# core6.net
KiCad netlist of a schematic drawn in EAGLE
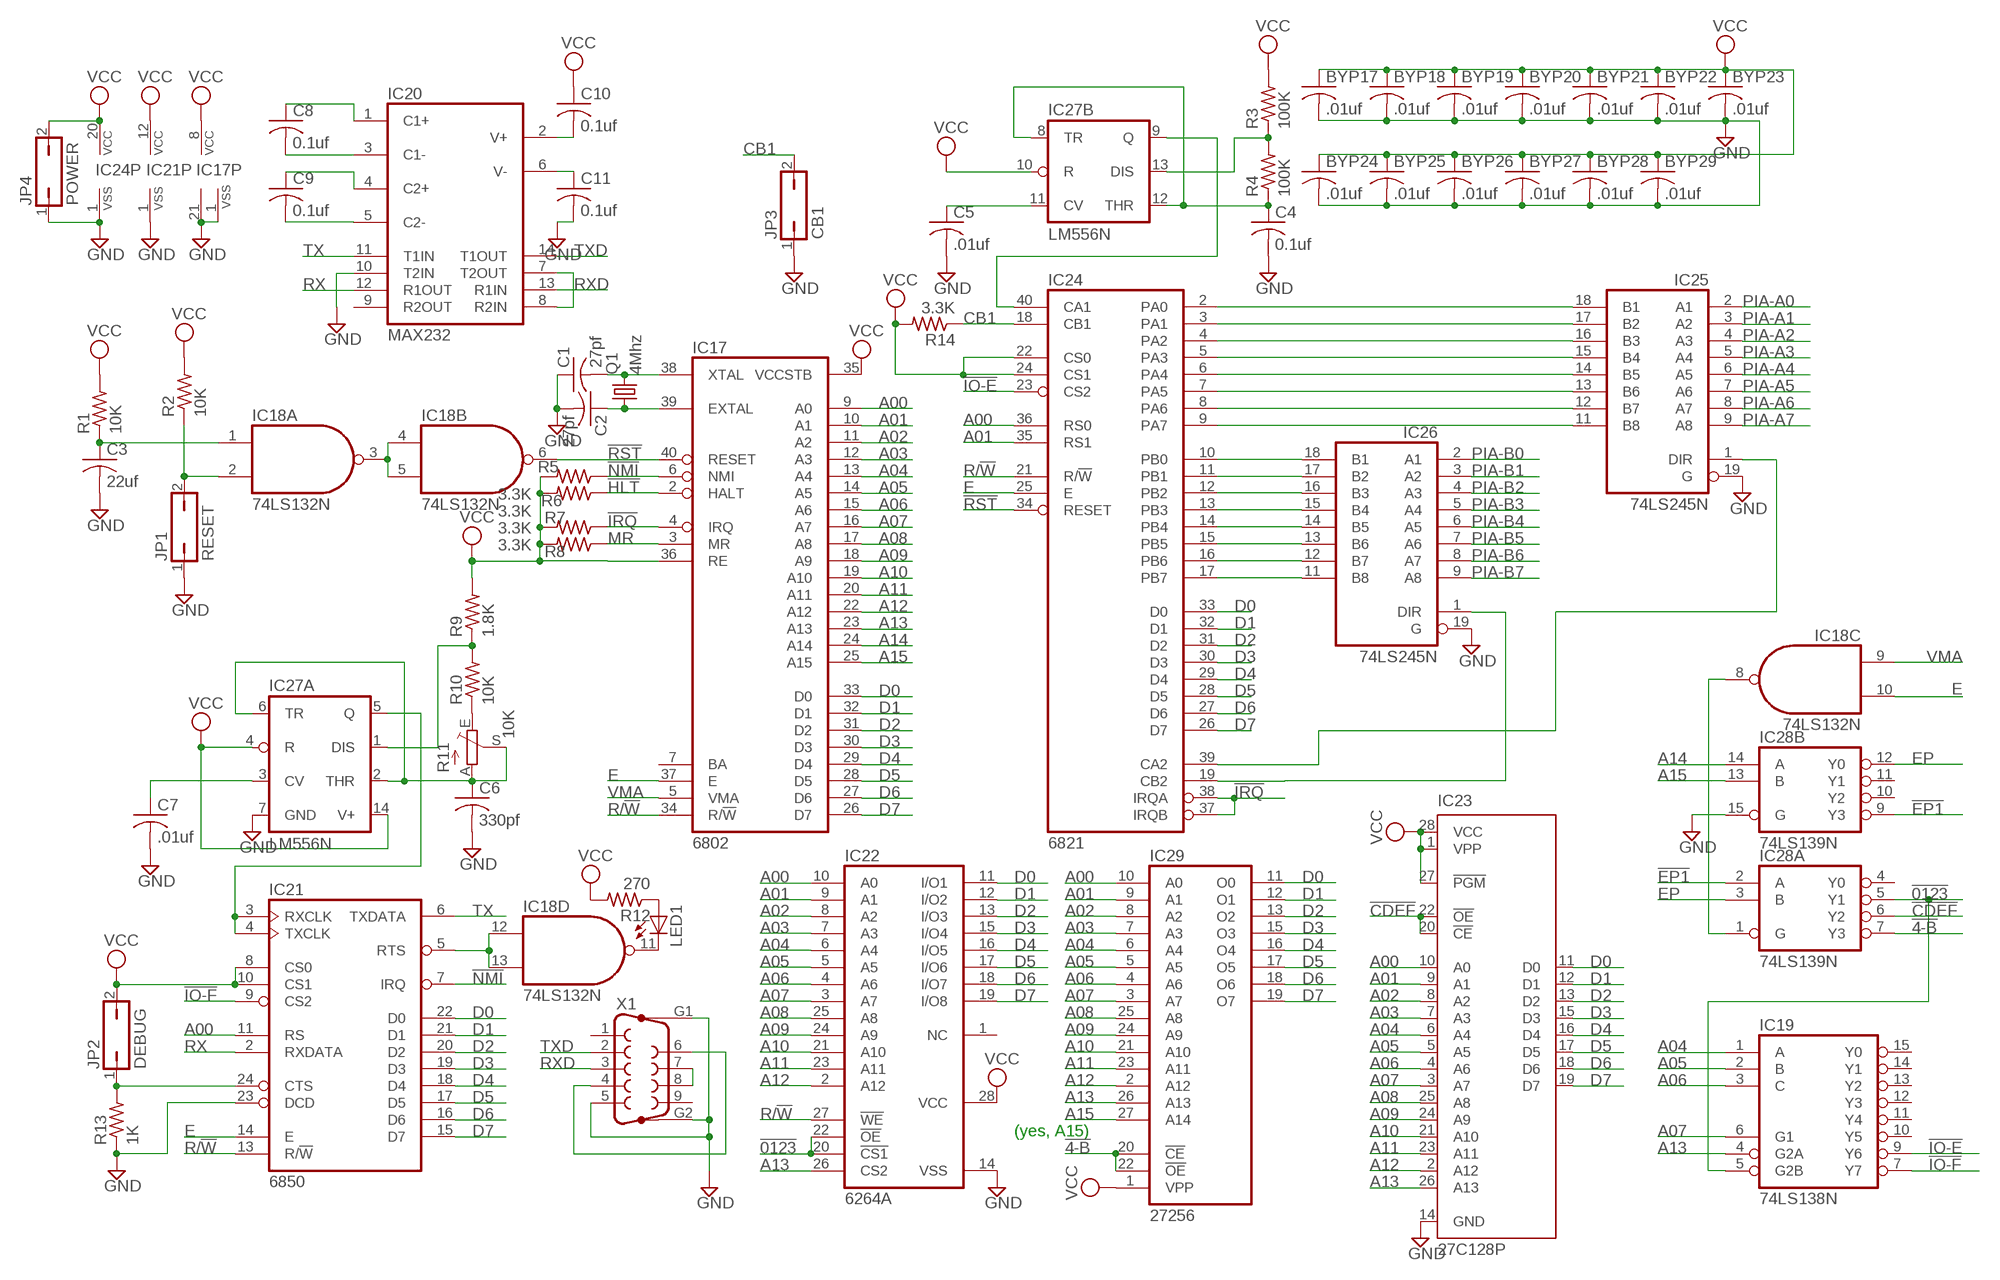
[diagram p0: schematic, sheet 1]
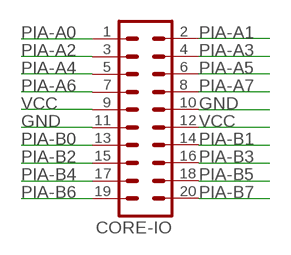
[diagram p1: schematic, sheet 2]

(export (version "E")
  (design (tool "Eeschema 10.0.6"))
  (components
    (comp (ref "BYP17")
      (value ".01uf")
      (footprint "eagle-import:C050-025X075")
      (libsource (lib "eagle-import") (part "C-US050-025X075"))
    )
    (comp (ref "BYP18")
      (value ".01uf")
      (footprint "eagle-import:C050-025X075")
      (libsource (lib "eagle-import") (part "C-US050-025X075"))
    )
    (comp (ref "BYP19")
      (value ".01uf")
      (footprint "eagle-import:C050-025X075")
      (libsource (lib "eagle-import") (part "C-US050-025X075"))
    )
    (comp (ref "BYP20")
      (value ".01uf")
      (footprint "eagle-import:C050-025X075")
      (libsource (lib "eagle-import") (part "C-US050-025X075"))
    )
    (comp (ref "BYP21")
      (value ".01uf")
      (footprint "eagle-import:C050-025X075")
      (libsource (lib "eagle-import") (part "C-US050-025X075"))
    )
    (comp (ref "BYP22")
      (value ".01uf")
      (footprint "eagle-import:C050-025X075")
      (libsource (lib "eagle-import") (part "C-US050-025X075"))
    )
    (comp (ref "BYP23")
      (value ".01uf")
      (footprint "eagle-import:C050-025X075")
      (libsource (lib "eagle-import") (part "C-US050-025X075"))
    )
    (comp (ref "BYP24")
      (value ".01uf")
      (footprint "eagle-import:C050-025X075")
      (libsource (lib "eagle-import") (part "C-US050-025X075"))
    )
    (comp (ref "BYP25")
      (value ".01uf")
      (footprint "eagle-import:C050-025X075")
      (libsource (lib "eagle-import") (part "C-US050-025X075"))
    )
    (comp (ref "BYP26")
      (value ".01uf")
      (footprint "eagle-import:C050-025X075")
      (libsource (lib "eagle-import") (part "C-US050-025X075"))
    )
    (comp (ref "BYP27")
      (value ".01uf")
      (footprint "eagle-import:C050-025X075")
      (libsource (lib "eagle-import") (part "C-US050-025X075"))
    )
    (comp (ref "BYP28")
      (value ".01uf")
      (footprint "eagle-import:C050-025X075")
      (libsource (lib "eagle-import") (part "C-US050-025X075"))
    )
    (comp (ref "BYP29")
      (value ".01uf")
      (footprint "eagle-import:C050-025X075")
      (libsource (lib "eagle-import") (part "C-US050-025X075"))
    )
    (comp (ref "C1")
      (value "27pf")
      (footprint "eagle-import:C050-025X075")
      (libsource (lib "eagle-import") (part "C-US050-025X075"))
    )
    (comp (ref "C2")
      (value "27pf")
      (footprint "eagle-import:C050-025X075")
      (libsource (lib "eagle-import") (part "C-US050-025X075"))
    )
    (comp (ref "C3")
      (value "22uf")
      (footprint "eagle-import:C102-043X133")
      (libsource (lib "eagle-import") (part "C-US102-043X133"))
    )
    (comp (ref "C4")
      (value "0.1uf")
      (footprint "eagle-import:C050-025X075")
      (libsource (lib "eagle-import") (part "C-US050-025X075"))
    )
    (comp (ref "C5")
      (value ".01uf")
      (footprint "eagle-import:C050-025X075")
      (libsource (lib "eagle-import") (part "C-US050-025X075"))
    )
    (comp (ref "C6")
      (value "330pf")
      (footprint "eagle-import:C050-025X075")
      (libsource (lib "eagle-import") (part "C-US050-025X075"))
    )
    (comp (ref "C7")
      (value ".01uf")
      (footprint "eagle-import:C050-025X075")
      (libsource (lib "eagle-import") (part "C-US050-025X075"))
    )
    (comp (ref "C8")
      (value "0.1uf")
      (footprint "eagle-import:C050-025X075")
      (libsource (lib "eagle-import") (part "C-US050-025X075"))
    )
    (comp (ref "C9")
      (value "0.1uf")
      (footprint "eagle-import:C050-025X075")
      (libsource (lib "eagle-import") (part "C-US050-025X075"))
    )
    (comp (ref "C10")
      (value "0.1uf")
      (footprint "eagle-import:C050-025X075")
      (libsource (lib "eagle-import") (part "C-US050-025X075"))
    )
    (comp (ref "C11")
      (value "0.1uf")
      (footprint "eagle-import:C050-025X075")
      (libsource (lib "eagle-import") (part "C-US050-025X075"))
    )
    (comp (ref "IC17")
      (value "6802")
      (footprint "eagle-import:DIL40")
      (libsource (lib "eagle-import") (part "6802"))
    )
    (comp (ref "IC18")
      (value "74LS132N")
      (footprint "eagle-import:DIL14")
      (libsource (lib "eagle-import") (part "7400NLS"))
    )
    (comp (ref "IC19")
      (value "74LS138N")
      (footprint "eagle-import:DIL16")
      (libsource (lib "eagle-import") (part "74138NLS"))
    )
    (comp (ref "IC20")
      (value "MAX232")
      (footprint "eagle-import:DIL16")
      (fields (field (name "MF") "MAXIM") (field (name "MPN") "MAX232ACPE+"))
      (libsource (lib "eagle-import") (part "MAX232"))
    )
    (comp (ref "IC21")
      (value "6850")
      (footprint "eagle-import:DIL24")
      (fields (field (name "MF") "NTE ELECTRONICS") (field (name "MPN") "NTE6850"))
      (libsource (lib "eagle-import") (part "6850"))
    )
    (comp (ref "IC22")
      (value "6264A")
      (footprint "eagle-import:DIL28-6")
      (libsource (lib "eagle-import") (part "6264A"))
    )
    (comp (ref "IC23")
      (value "27C128P")
      (footprint "eagle-import:DIL28-6")
      (libsource (lib "eagle-import") (part "27128PC"))
    )
    (comp (ref "IC24")
      (value "6821")
      (footprint "eagle-import:DIL40")
      (fields (field (name "MF") "NTE ELECTRONICS") (field (name "MPN") "NTE6821"))
      (libsource (lib "eagle-import") (part "6821"))
    )
    (comp (ref "IC25")
      (value "74LS245N")
      (footprint "eagle-import:DIL20")
      (libsource (lib "eagle-import") (part "74245NLS"))
    )
    (comp (ref "IC26")
      (value "74LS245N")
      (footprint "eagle-import:DIL20")
      (libsource (lib "eagle-import") (part "74245NLS"))
    )
    (comp (ref "IC27")
      (value "LM556N")
      (footprint "eagle-import:DIL14")
      (libsource (lib "eagle-import") (part "556NLM"))
    )
    (comp (ref "IC28")
      (value "74LS139N")
      (footprint "eagle-import:DIL16")
      (libsource (lib "eagle-import") (part "74139NLS"))
    )
    (comp (ref "IC29")
      (value "27256")
      (footprint "eagle-import:DIL28")
      (libsource (lib "eagle-import") (part "27256"))
    )
    (comp (ref "JP1")
      (value "RESET")
      (footprint "eagle-import:JP1")
      (libsource (lib "eagle-import") (part "JP1Q"))
    )
    (comp (ref "JP2")
      (value "DEBUG")
      (footprint "eagle-import:JP1")
      (libsource (lib "eagle-import") (part "JP1Q"))
    )
    (comp (ref "JP3")
      (value "CB1")
      (footprint "eagle-import:JP1")
      (libsource (lib "eagle-import") (part "JP1Q"))
    )
    (comp (ref "JP4")
      (value "POWER")
      (footprint "eagle-import:JP1")
      (libsource (lib "eagle-import") (part "JP1Q"))
    )
    (comp (ref "LED1")
      (value "LED3MM")
      (footprint "eagle-import:LED3MM")
      (libsource (lib "eagle-import") (part "LED3MM"))
    )
    (comp (ref "Q1")
      (value "4Mhz")
      (footprint "eagle-import:HC18U-V")
      (libsource (lib "eagle-import") (part "CRYSTALHC18U-V"))
    )
    (comp (ref "R1")
      (value "10K")
      (footprint "eagle-import:0207_7")
      (libsource (lib "eagle-import") (part "R-US_0207/7"))
    )
    (comp (ref "R2")
      (value "10K")
      (footprint "eagle-import:0207_7")
      (libsource (lib "eagle-import") (part "R-US_0207/7"))
    )
    (comp (ref "R3")
      (value "100K")
      (footprint "eagle-import:0207_7")
      (libsource (lib "eagle-import") (part "R-US_0207/7"))
    )
    (comp (ref "R4")
      (value "100K")
      (footprint "eagle-import:0207_7")
      (libsource (lib "eagle-import") (part "R-US_0207/7"))
    )
    (comp (ref "R5")
      (value "3.3K")
      (footprint "eagle-import:0207_7")
      (libsource (lib "eagle-import") (part "R-US_0207/7"))
    )
    (comp (ref "R6")
      (value "3.3K")
      (footprint "eagle-import:0207_7")
      (libsource (lib "eagle-import") (part "R-US_0207/7"))
    )
    (comp (ref "R7")
      (value "3.3K")
      (footprint "eagle-import:0207_7")
      (libsource (lib "eagle-import") (part "R-US_0207/7"))
    )
    (comp (ref "R8")
      (value "3.3K")
      (footprint "eagle-import:0207_7")
      (libsource (lib "eagle-import") (part "R-US_0207/7"))
    )
    (comp (ref "R9")
      (value "1.8K")
      (footprint "eagle-import:0207_7")
      (libsource (lib "eagle-import") (part "R-US_0207/7"))
    )
    (comp (ref "R10")
      (value "10K")
      (footprint "eagle-import:0207_7")
      (libsource (lib "eagle-import") (part "R-US_0207/7"))
    )
    (comp (ref "R11")
      (value "10K")
      (footprint "eagle-import:SP19L")
      (libsource (lib "eagle-import") (part "TRIM_EU-B90P"))
    )
    (comp (ref "R12")
      (value "270")
      (footprint "eagle-import:0207_7")
      (libsource (lib "eagle-import") (part "R-US_0207/7"))
    )
    (comp (ref "R13")
      (value "1K")
      (footprint "eagle-import:0207_7")
      (libsource (lib "eagle-import") (part "R-US_0207/7"))
    )
    (comp (ref "R14")
      (value "3.3K")
      (footprint "eagle-import:0207_7")
      (libsource (lib "eagle-import") (part "R-US_0207/7"))
    )
    (comp (ref "X1")
      (value "F09HP")
      (footprint "eagle-import:F09HP")
      (libsource (lib "eagle-import") (part "F09HP"))
    )
    (comp (ref "CORE-IO")
      (value "MA10-2")
      (footprint "eagle-import:MA10-2")
      (libsource (lib "eagle-import") (part "MA10-2"))
    )
  )
  (nets
    (net (code "1") (name "A00") (class "Default")
      (node (ref "IC17") (pin "9") (pinfunction "A0_9") (pintype "output"))
      (node (ref "IC21") (pin "11") (pinfunction "RS_11") (pintype "input"))
      (node (ref "IC22") (pin "10") (pinfunction "A0_10") (pintype "input"))
      (node (ref "IC23") (pin "10") (pinfunction "A0_10") (pintype "input"))
      (node (ref "IC24") (pin "36") (pinfunction "RS0_36") (pintype "input"))
      (node (ref "IC29") (pin "10") (pinfunction "A0_10") (pintype "input"))
    )
    (net (code "2") (name "A01") (class "Default")
      (node (ref "IC17") (pin "10") (pinfunction "A1_10") (pintype "output"))
      (node (ref "IC22") (pin "9") (pinfunction "A1_9") (pintype "input"))
      (node (ref "IC23") (pin "9") (pinfunction "A1_9") (pintype "input"))
      (node (ref "IC24") (pin "35") (pinfunction "RS1_35") (pintype "input"))
      (node (ref "IC29") (pin "9") (pinfunction "A1_9") (pintype "input"))
    )
    (net (code "3") (name "A02") (class "Default")
      (node (ref "IC17") (pin "11") (pinfunction "A2_11") (pintype "output"))
      (node (ref "IC22") (pin "8") (pinfunction "A2_8") (pintype "input"))
      (node (ref "IC23") (pin "8") (pinfunction "A2_8") (pintype "input"))
      (node (ref "IC29") (pin "8") (pinfunction "A2_8") (pintype "input"))
    )
    (net (code "4") (name "A03") (class "Default")
      (node (ref "IC17") (pin "12") (pinfunction "A3_12") (pintype "output"))
      (node (ref "IC22") (pin "7") (pinfunction "A3_7") (pintype "input"))
      (node (ref "IC23") (pin "7") (pinfunction "A3_7") (pintype "input"))
      (node (ref "IC29") (pin "7") (pinfunction "A3_7") (pintype "input"))
    )
    (net (code "5") (name "A04") (class "Default")
      (node (ref "IC17") (pin "13") (pinfunction "A4_13") (pintype "output"))
      (node (ref "IC19") (pin "1") (pinfunction "A_1") (pintype "input"))
      (node (ref "IC22") (pin "6") (pinfunction "A4_6") (pintype "input"))
      (node (ref "IC23") (pin "6") (pinfunction "A4_6") (pintype "input"))
      (node (ref "IC29") (pin "6") (pinfunction "A4_6") (pintype "input"))
    )
    (net (code "6") (name "A05") (class "Default")
      (node (ref "IC17") (pin "14") (pinfunction "A5_14") (pintype "output"))
      (node (ref "IC19") (pin "2") (pinfunction "B_2") (pintype "input"))
      (node (ref "IC22") (pin "5") (pinfunction "A5_5") (pintype "input"))
      (node (ref "IC23") (pin "5") (pinfunction "A5_5") (pintype "input"))
      (node (ref "IC29") (pin "5") (pinfunction "A5_5") (pintype "input"))
    )
    (net (code "7") (name "A06") (class "Default")
      (node (ref "IC17") (pin "15") (pinfunction "A6_15") (pintype "output"))
      (node (ref "IC19") (pin "3") (pinfunction "C_3") (pintype "input"))
      (node (ref "IC22") (pin "4") (pinfunction "A6_4") (pintype "input"))
      (node (ref "IC23") (pin "4") (pinfunction "A6_4") (pintype "input"))
      (node (ref "IC29") (pin "4") (pinfunction "A6_4") (pintype "input"))
    )
    (net (code "8") (name "A07") (class "Default")
      (node (ref "IC17") (pin "16") (pinfunction "A7_16") (pintype "output"))
      (node (ref "IC19") (pin "6") (pinfunction "G1_6") (pintype "input"))
      (node (ref "IC22") (pin "3") (pinfunction "A7_3") (pintype "input"))
      (node (ref "IC23") (pin "3") (pinfunction "A7_3") (pintype "input"))
      (node (ref "IC29") (pin "3") (pinfunction "A7_3") (pintype "input"))
    )
    (net (code "9") (name "A08") (class "Default")
      (node (ref "IC17") (pin "17") (pinfunction "A8_17") (pintype "output"))
      (node (ref "IC22") (pin "25") (pinfunction "A8_25") (pintype "input"))
      (node (ref "IC23") (pin "25") (pinfunction "A8_25") (pintype "input"))
      (node (ref "IC29") (pin "25") (pinfunction "A8_25") (pintype "input"))
    )
    (net (code "10") (name "A09") (class "Default")
      (node (ref "IC17") (pin "18") (pinfunction "A9_18") (pintype "output"))
      (node (ref "IC22") (pin "24") (pinfunction "A9_24") (pintype "input"))
      (node (ref "IC23") (pin "24") (pinfunction "A9_24") (pintype "input"))
      (node (ref "IC29") (pin "24") (pinfunction "A9_24") (pintype "input"))
    )
    (net (code "11") (name "A10") (class "Default")
      (node (ref "IC17") (pin "19") (pinfunction "A10_19") (pintype "output"))
      (node (ref "IC22") (pin "21") (pinfunction "A10_21") (pintype "input"))
      (node (ref "IC23") (pin "21") (pinfunction "A10_21") (pintype "input"))
      (node (ref "IC29") (pin "21") (pinfunction "A10_21") (pintype "input"))
    )
    (net (code "12") (name "A11") (class "Default")
      (node (ref "IC17") (pin "20") (pinfunction "A11_20") (pintype "output"))
      (node (ref "IC22") (pin "23") (pinfunction "A11_23") (pintype "input"))
      (node (ref "IC23") (pin "23") (pinfunction "A11_23") (pintype "input"))
      (node (ref "IC29") (pin "23") (pinfunction "A11_23") (pintype "input"))
    )
    (net (code "13") (name "A12") (class "Default")
      (node (ref "IC17") (pin "22") (pinfunction "A12_22") (pintype "output"))
      (node (ref "IC22") (pin "2") (pinfunction "A12_2") (pintype "input"))
      (node (ref "IC23") (pin "2") (pinfunction "A12_2") (pintype "input"))
      (node (ref "IC29") (pin "2") (pinfunction "A12_2") (pintype "input"))
    )
    (net (code "14") (name "A13") (class "Default")
      (node (ref "IC17") (pin "23") (pinfunction "A13_23") (pintype "output"))
      (node (ref "IC19") (pin "4") (pinfunction "G2A_4") (pintype "input"))
      (node (ref "IC22") (pin "26") (pinfunction "CS2_26") (pintype "input"))
      (node (ref "IC23") (pin "26") (pinfunction "A13_26") (pintype "input"))
      (node (ref "IC29") (pin "26") (pinfunction "A13_26") (pintype "input"))
    )
    (net (code "15") (name "A14") (class "Default")
      (node (ref "IC17") (pin "24") (pinfunction "A14_24") (pintype "output"))
      (node (ref "IC28") (pin "14") (pinfunction "A_14") (pintype "input"))
    )
    (net (code "16") (name "A15") (class "Default")
      (node (ref "IC17") (pin "25") (pinfunction "A15_25") (pintype "output"))
      (node (ref "IC28") (pin "13") (pinfunction "B_13") (pintype "input"))
      (node (ref "IC29") (pin "27") (pinfunction "A14_27") (pintype "input"))
    )
    (net (code "17") (name "CB1") (class "Default")
      (node (ref "IC24") (pin "18") (pinfunction "CB1_18") (pintype "input"))
      (node (ref "JP3") (pin "2") (pinfunction "2_2") (pintype "passive"))
      (node (ref "R14") (pin "1") (pinfunction "1_1") (pintype "passive"))
    )
    (net (code "18") (name "D0") (class "Default")
      (node (ref "IC17") (pin "33") (pinfunction "D0_33") (pintype "bidirectional"))
      (node (ref "IC21") (pin "22") (pinfunction "D0_22") (pintype "bidirectional"))
      (node (ref "IC22") (pin "11") (pinfunction "I/O1_11") (pintype "bidirectional"))
      (node (ref "IC23") (pin "11") (pinfunction "D0_11") (pintype "tri_state"))
      (node (ref "IC24") (pin "33") (pinfunction "D0_33") (pintype "bidirectional"))
      (node (ref "IC29") (pin "11") (pinfunction "O0_11") (pintype "tri_state"))
    )
    (net (code "19") (name "D1") (class "Default")
      (node (ref "IC17") (pin "32") (pinfunction "D1_32") (pintype "bidirectional"))
      (node (ref "IC21") (pin "21") (pinfunction "D1_21") (pintype "bidirectional"))
      (node (ref "IC22") (pin "12") (pinfunction "I/O2_12") (pintype "bidirectional"))
      (node (ref "IC23") (pin "12") (pinfunction "D1_12") (pintype "tri_state"))
      (node (ref "IC24") (pin "32") (pinfunction "D1_32") (pintype "bidirectional"))
      (node (ref "IC29") (pin "12") (pinfunction "O1_12") (pintype "tri_state"))
    )
    (net (code "20") (name "D2") (class "Default")
      (node (ref "IC17") (pin "31") (pinfunction "D2_31") (pintype "bidirectional"))
      (node (ref "IC21") (pin "20") (pinfunction "D2_20") (pintype "bidirectional"))
      (node (ref "IC22") (pin "13") (pinfunction "I/O3_13") (pintype "bidirectional"))
      (node (ref "IC23") (pin "13") (pinfunction "D2_13") (pintype "tri_state"))
      (node (ref "IC24") (pin "31") (pinfunction "D2_31") (pintype "bidirectional"))
      (node (ref "IC29") (pin "13") (pinfunction "O2_13") (pintype "tri_state"))
    )
    (net (code "21") (name "D3") (class "Default")
      (node (ref "IC17") (pin "30") (pinfunction "D3_30") (pintype "bidirectional"))
      (node (ref "IC21") (pin "19") (pinfunction "D3_19") (pintype "bidirectional"))
      (node (ref "IC22") (pin "15") (pinfunction "I/O4_15") (pintype "bidirectional"))
      (node (ref "IC23") (pin "15") (pinfunction "D3_15") (pintype "tri_state"))
      (node (ref "IC24") (pin "30") (pinfunction "D3_30") (pintype "bidirectional"))
      (node (ref "IC29") (pin "15") (pinfunction "O3_15") (pintype "tri_state"))
    )
    (net (code "22") (name "D4") (class "Default")
      (node (ref "IC17") (pin "29") (pinfunction "D4_29") (pintype "bidirectional"))
      (node (ref "IC21") (pin "18") (pinfunction "D4_18") (pintype "bidirectional"))
      (node (ref "IC22") (pin "16") (pinfunction "I/O5_16") (pintype "bidirectional"))
      (node (ref "IC23") (pin "16") (pinfunction "D4_16") (pintype "tri_state"))
      (node (ref "IC24") (pin "29") (pinfunction "D4_29") (pintype "bidirectional"))
      (node (ref "IC29") (pin "16") (pinfunction "O4_16") (pintype "tri_state"))
    )
    (net (code "23") (name "D5") (class "Default")
      (node (ref "IC17") (pin "28") (pinfunction "D5_28") (pintype "bidirectional"))
      (node (ref "IC21") (pin "17") (pinfunction "D5_17") (pintype "bidirectional"))
      (node (ref "IC22") (pin "17") (pinfunction "I/O6_17") (pintype "bidirectional"))
      (node (ref "IC23") (pin "17") (pinfunction "D5_17") (pintype "tri_state"))
      (node (ref "IC24") (pin "28") (pinfunction "D5_28") (pintype "bidirectional"))
      (node (ref "IC29") (pin "17") (pinfunction "O5_17") (pintype "tri_state"))
    )
    (net (code "24") (name "D6") (class "Default")
      (node (ref "IC17") (pin "27") (pinfunction "D6_27") (pintype "bidirectional"))
      (node (ref "IC21") (pin "16") (pinfunction "D6_16") (pintype "bidirectional"))
      (node (ref "IC22") (pin "18") (pinfunction "I/O7_18") (pintype "bidirectional"))
      (node (ref "IC23") (pin "18") (pinfunction "D6_18") (pintype "tri_state"))
      (node (ref "IC24") (pin "27") (pinfunction "D6_27") (pintype "bidirectional"))
      (node (ref "IC29") (pin "18") (pinfunction "O6_18") (pintype "tri_state"))
    )
    (net (code "25") (name "D7") (class "Default")
      (node (ref "IC17") (pin "26") (pinfunction "D7_26") (pintype "bidirectional"))
      (node (ref "IC21") (pin "15") (pinfunction "D7_15") (pintype "bidirectional"))
      (node (ref "IC22") (pin "19") (pinfunction "I/O8_19") (pintype "bidirectional"))
      (node (ref "IC23") (pin "19") (pinfunction "D7_19") (pintype "tri_state"))
      (node (ref "IC24") (pin "26") (pinfunction "D7_26") (pintype "bidirectional"))
      (node (ref "IC29") (pin "19") (pinfunction "O7_19") (pintype "tri_state"))
    )
    (net (code "26") (name "E") (class "Default")
      (node (ref "IC17") (pin "37") (pinfunction "E_37") (pintype "output"))
      (node (ref "IC18") (pin "10") (pinfunction "I1_10") (pintype "input"))
      (node (ref "IC21") (pin "14") (pinfunction "E_14") (pintype "input"))
      (node (ref "IC24") (pin "25") (pinfunction "E_25") (pintype "input"))
    )
    (net (code "27") (name "EP") (class "Default")
      (node (ref "IC28") (pin "12") (pinfunction "Y0_12") (pintype "output"))
      (node (ref "IC28") (pin "3") (pinfunction "B_3") (pintype "input"))
    )
    (net (code "28") (name "GND") (class "Default")
      (node (ref "BYP17") (pin "2") (pinfunction "2_2") (pintype "passive"))
      (node (ref "BYP18") (pin "2") (pinfunction "2_2") (pintype "passive"))
      (node (ref "BYP19") (pin "2") (pinfunction "2_2") (pintype "passive"))
      (node (ref "BYP20") (pin "2") (pinfunction "2_2") (pintype "passive"))
      (node (ref "BYP21") (pin "2") (pinfunction "2_2") (pintype "passive"))
      (node (ref "BYP22") (pin "2") (pinfunction "2_2") (pintype "passive"))
      (node (ref "BYP23") (pin "2") (pinfunction "2_2") (pintype "passive"))
      (node (ref "BYP24") (pin "2") (pinfunction "2_2") (pintype "passive"))
      (node (ref "BYP25") (pin "2") (pinfunction "2_2") (pintype "passive"))
      (node (ref "BYP26") (pin "2") (pinfunction "2_2") (pintype "passive"))
      (node (ref "BYP27") (pin "2") (pinfunction "2_2") (pintype "passive"))
      (node (ref "BYP28") (pin "2") (pinfunction "2_2") (pintype "passive"))
      (node (ref "BYP29") (pin "2") (pinfunction "2_2") (pintype "passive"))
      (node (ref "C1") (pin "1") (pinfunction "1_1") (pintype "passive"))
      (node (ref "C11") (pin "2") (pinfunction "2_2") (pintype "passive"))
      (node (ref "C2") (pin "2") (pinfunction "2_2") (pintype "passive"))
      (node (ref "C3") (pin "2") (pinfunction "2_2") (pintype "passive"))
      (node (ref "C4") (pin "2") (pinfunction "2_2") (pintype "passive"))
      (node (ref "C5") (pin "2") (pinfunction "2_2") (pintype "passive"))
      (node (ref "C6") (pin "2") (pinfunction "2_2") (pintype "passive"))
      (node (ref "C7") (pin "2") (pinfunction "2_2") (pintype "passive"))
      (node (ref "CORE-IO") (pin "10") (pinfunction "10_10") (pintype "passive"))
      (node (ref "CORE-IO") (pin "11") (pinfunction "11_11") (pintype "passive"))
      (node (ref "IC17") (pin "1") (pinfunction "VSS_1") (pintype "power_in"))
      (node (ref "IC17") (pin "21") (pinfunction "VSS_21") (pintype "power_in"))
      (node (ref "IC20") (pin "10") (pinfunction "T2IN_10") (pintype "input"))
      (node (ref "IC21") (pin "1") (pinfunction "VSS_1") (pintype "power_in"))
      (node (ref "IC21") (pin "23") (pinfunction "DCD_23") (pintype "input"))
      (node (ref "IC22") (pin "14") (pinfunction "VSS_14") (pintype "power_in"))
      (node (ref "IC23") (pin "14") (pinfunction "GND_14") (pintype "power_in"))
      (node (ref "IC24") (pin "1") (pinfunction "VSS_1") (pintype "power_in"))
      (node (ref "IC25") (pin "19") (pinfunction "G_19") (pintype "input"))
      (node (ref "IC26") (pin "19") (pinfunction "G_19") (pintype "input"))
      (node (ref "IC27") (pin "7") (pinfunction "GND_7") (pintype "power_in"))
      (node (ref "IC28") (pin "15") (pinfunction "G_15") (pintype "input"))
      (node (ref "JP1") (pin "1") (pinfunction "1_1") (pintype "passive"))
      (node (ref "JP3") (pin "1") (pinfunction "1_1") (pintype "passive"))
      (node (ref "JP4") (pin "1") (pinfunction "1_1") (pintype "passive"))
      (node (ref "R13") (pin "1") (pinfunction "1_1") (pintype "passive"))
      (node (ref "X1") (pin "5") (pinfunction "5_5") (pintype "passive"))
      (node (ref "X1") (pin "G1") (pinfunction "G1_G1") (pintype "passive"))
      (node (ref "X1") (pin "G2") (pinfunction "G2_G2") (pintype "passive"))
    )
    (net (code "29") (name "MR") (class "Default")
      (node (ref "IC17") (pin "3") (pinfunction "MR_3") (pintype "input"))
      (node (ref "R8") (pin "1") (pinfunction "1_1") (pintype "passive"))
    )
    (net (code "30") (name "Net-(IC17A-EXTAL)") (class "Default")
      (node (ref "C2") (pin "1") (pinfunction "1_1") (pintype "passive"))
      (node (ref "IC17") (pin "39") (pinfunction "EXTAL_39") (pintype "input"))
      (node (ref "Q1") (pin "1") (pinfunction "1_1") (pintype "passive"))
    )
    (net (code "31") (name "Net-(IC17A-XTAL)") (class "Default")
      (node (ref "C1") (pin "2") (pinfunction "2_2") (pintype "passive"))
      (node (ref "IC17") (pin "38") (pinfunction "XTAL_38") (pintype "input"))
      (node (ref "Q1") (pin "2") (pinfunction "2_2") (pintype "passive"))
    )
    (net (code "32") (name "Net-(IC18A-I0)") (class "Default")
      (node (ref "C3") (pin "1") (pinfunction "1_1") (pintype "passive"))
      (node (ref "IC18") (pin "1") (pinfunction "I0_1") (pintype "input"))
      (node (ref "R1") (pin "1") (pinfunction "1_1") (pintype "passive"))
    )
    (net (code "33") (name "Net-(IC18A-I1)") (class "Default")
      (node (ref "IC18") (pin "2") (pinfunction "I1_2") (pintype "input"))
      (node (ref "JP1") (pin "2") (pinfunction "2_2") (pintype "passive"))
      (node (ref "R2") (pin "1") (pinfunction "1_1") (pintype "passive"))
    )
    (net (code "34") (name "Net-(IC18A-O)") (class "Default")
      (node (ref "IC18") (pin "3") (pinfunction "O_3") (pintype "output"))
      (node (ref "IC18") (pin "4") (pinfunction "I0_4") (pintype "input"))
      (node (ref "IC18") (pin "5") (pinfunction "I1_5") (pintype "input"))
    )
    (net (code "35") (name "Net-(IC18C-O)") (class "Default")
      (node (ref "IC18") (pin "8") (pinfunction "O_8") (pintype "output"))
      (node (ref "IC28") (pin "1") (pinfunction "G_1") (pintype "input"))
    )
    (net (code "36") (name "Net-(IC18D-I0)") (class "Default")
      (node (ref "IC18") (pin "12") (pinfunction "I0_12") (pintype "input"))
      (node (ref "IC18") (pin "13") (pinfunction "I1_13") (pintype "input"))
      (node (ref "IC21") (pin "5") (pinfunction "RTS_5") (pintype "output"))
    )
    (net (code "37") (name "Net-(IC18D-O)") (class "Default")
      (node (ref "IC18") (pin "11") (pinfunction "O_11") (pintype "output"))
      (node (ref "LED1") (pin "K") (pinfunction "C_K") (pintype "passive"))
    )
    (net (code "38") (name "Net-(IC20A-C1+)") (class "Default")
      (node (ref "C8") (pin "1") (pinfunction "1_1") (pintype "passive"))
      (node (ref "IC20") (pin "1") (pinfunction "C1+_1") (pintype "bidirectional"))
    )
    (net (code "39") (name "Net-(IC20A-C1-)") (class "Default")
      (node (ref "C8") (pin "2") (pinfunction "2_2") (pintype "passive"))
      (node (ref "IC20") (pin "3") (pinfunction "C1-_3") (pintype "bidirectional"))
    )
    (net (code "40") (name "Net-(IC20A-C2+)") (class "Default")
      (node (ref "C9") (pin "1") (pinfunction "1_1") (pintype "passive"))
      (node (ref "IC20") (pin "4") (pinfunction "C2+_4") (pintype "bidirectional"))
    )
    (net (code "41") (name "Net-(IC20A-C2-)") (class "Default")
      (node (ref "C9") (pin "2") (pinfunction "2_2") (pintype "passive"))
      (node (ref "IC20") (pin "5") (pinfunction "C2-_5") (pintype "bidirectional"))
    )
    (net (code "42") (name "Net-(IC20A-R2IN)") (class "Default")
      (node (ref "IC20") (pin "7") (pinfunction "T2OUT_7") (pintype "output"))
      (node (ref "IC20") (pin "8") (pinfunction "R2IN_8") (pintype "input"))
    )
    (net (code "43") (name "Net-(IC20A-V+)") (class "Default")
      (node (ref "C10") (pin "2") (pinfunction "2_2") (pintype "passive"))
      (node (ref "IC20") (pin "2") (pinfunction "V+_2") (pintype "bidirectional"))
    )
    (net (code "44") (name "Net-(IC20A-V-)") (class "Default")
      (node (ref "C11") (pin "1") (pinfunction "1_1") (pintype "passive"))
      (node (ref "IC20") (pin "6") (pinfunction "V-_6") (pintype "bidirectional"))
    )
    (net (code "45") (name "Net-(IC21A-CTS)") (class "Default")
      (node (ref "IC21") (pin "24") (pinfunction "CTS_24") (pintype "input"))
      (node (ref "JP2") (pin "1") (pinfunction "1_1") (pintype "passive"))
      (node (ref "R13") (pin "2") (pinfunction "2_2") (pintype "passive"))
    )
    (net (code "46") (name "Net-(IC21A-RXCLK)") (class "Default")
      (node (ref "IC21") (pin "3") (pinfunction "RXCLK_3") (pintype "input"))
      (node (ref "IC21") (pin "4") (pinfunction "TXCLK_4") (pintype "input"))
      (node (ref "IC27") (pin "5") (pinfunction "Q_5") (pintype "output"))
    )
    (net (code "47") (name "Net-(IC24A-CA1)") (class "Default")
      (node (ref "IC24") (pin "40") (pinfunction "CA1_40") (pintype "input"))
      (node (ref "IC27") (pin "9") (pinfunction "Q_9") (pintype "output"))
    )
    (net (code "48") (name "Net-(IC24A-CA2)") (class "Default")
      (node (ref "IC24") (pin "39") (pinfunction "CA2_39") (pintype "bidirectional"))
      (node (ref "IC25") (pin "1") (pinfunction "DIR_1") (pintype "input"))
    )
    (net (code "49") (name "Net-(IC24A-CB2)") (class "Default")
      (node (ref "IC24") (pin "19") (pinfunction "CB2_19") (pintype "bidirectional"))
      (node (ref "IC26") (pin "1") (pinfunction "DIR_1") (pintype "input"))
    )
    (net (code "50") (name "Net-(IC24A-PA0)") (class "Default")
      (node (ref "IC24") (pin "2") (pinfunction "PA0_2") (pintype "bidirectional"))
      (node (ref "IC25") (pin "18") (pinfunction "B1_18") (pintype "bidirectional"))
    )
    (net (code "51") (name "Net-(IC24A-PA1)") (class "Default")
      (node (ref "IC24") (pin "3") (pinfunction "PA1_3") (pintype "bidirectional"))
      (node (ref "IC25") (pin "17") (pinfunction "B2_17") (pintype "bidirectional"))
    )
    (net (code "52") (name "Net-(IC24A-PA2)") (class "Default")
      (node (ref "IC24") (pin "4") (pinfunction "PA2_4") (pintype "bidirectional"))
      (node (ref "IC25") (pin "16") (pinfunction "B3_16") (pintype "bidirectional"))
    )
    (net (code "53") (name "Net-(IC24A-PA3)") (class "Default")
      (node (ref "IC24") (pin "5") (pinfunction "PA3_5") (pintype "bidirectional"))
      (node (ref "IC25") (pin "15") (pinfunction "B4_15") (pintype "bidirectional"))
    )
    (net (code "54") (name "Net-(IC24A-PA4)") (class "Default")
      (node (ref "IC24") (pin "6") (pinfunction "PA4_6") (pintype "bidirectional"))
      (node (ref "IC25") (pin "14") (pinfunction "B5_14") (pintype "bidirectional"))
    )
    (net (code "55") (name "Net-(IC24A-PA5)") (class "Default")
      (node (ref "IC24") (pin "7") (pinfunction "PA5_7") (pintype "bidirectional"))
      (node (ref "IC25") (pin "13") (pinfunction "B6_13") (pintype "bidirectional"))
    )
    (net (code "56") (name "Net-(IC24A-PA6)") (class "Default")
      (node (ref "IC24") (pin "8") (pinfunction "PA6_8") (pintype "bidirectional"))
      (node (ref "IC25") (pin "12") (pinfunction "B7_12") (pintype "bidirectional"))
    )
    (net (code "57") (name "Net-(IC24A-PA7)") (class "Default")
      (node (ref "IC24") (pin "9") (pinfunction "PA7_9") (pintype "bidirectional"))
      (node (ref "IC25") (pin "11") (pinfunction "B8_11") (pintype "bidirectional"))
    )
    (net (code "58") (name "Net-(IC24A-PB0)") (class "Default")
      (node (ref "IC24") (pin "10") (pinfunction "PB0_10") (pintype "bidirectional"))
      (node (ref "IC26") (pin "18") (pinfunction "B1_18") (pintype "bidirectional"))
    )
    (net (code "59") (name "Net-(IC24A-PB1)") (class "Default")
      (node (ref "IC24") (pin "11") (pinfunction "PB1_11") (pintype "bidirectional"))
      (node (ref "IC26") (pin "17") (pinfunction "B2_17") (pintype "bidirectional"))
    )
    (net (code "60") (name "Net-(IC24A-PB2)") (class "Default")
      (node (ref "IC24") (pin "12") (pinfunction "PB2_12") (pintype "bidirectional"))
      (node (ref "IC26") (pin "16") (pinfunction "B3_16") (pintype "bidirectional"))
    )
    (net (code "61") (name "Net-(IC24A-PB3)") (class "Default")
      (node (ref "IC24") (pin "13") (pinfunction "PB3_13") (pintype "bidirectional"))
      (node (ref "IC26") (pin "15") (pinfunction "B4_15") (pintype "bidirectional"))
    )
    (net (code "62") (name "Net-(IC24A-PB4)") (class "Default")
      (node (ref "IC24") (pin "14") (pinfunction "PB4_14") (pintype "bidirectional"))
      (node (ref "IC26") (pin "14") (pinfunction "B5_14") (pintype "bidirectional"))
    )
    (net (code "63") (name "Net-(IC24A-PB5)") (class "Default")
      (node (ref "IC24") (pin "15") (pinfunction "PB5_15") (pintype "bidirectional"))
      (node (ref "IC26") (pin "13") (pinfunction "B6_13") (pintype "bidirectional"))
    )
    (net (code "64") (name "Net-(IC24A-PB6)") (class "Default")
      (node (ref "IC24") (pin "16") (pinfunction "PB6_16") (pintype "bidirectional"))
      (node (ref "IC26") (pin "12") (pinfunction "B7_12") (pintype "bidirectional"))
    )
    (net (code "65") (name "Net-(IC24A-PB7)") (class "Default")
      (node (ref "IC24") (pin "17") (pinfunction "PB7_17") (pintype "bidirectional"))
      (node (ref "IC26") (pin "11") (pinfunction "B8_11") (pintype "bidirectional"))
    )
    (net (code "66") (name "Net-(IC27A-CV)") (class "Default")
      (node (ref "C7") (pin "1") (pinfunction "1_1") (pintype "passive"))
      (node (ref "IC27") (pin "3") (pinfunction "CV_3") (pintype "input"))
    )
    (net (code "67") (name "Net-(IC27A-DIS)") (class "Default")
      (node (ref "IC27") (pin "1") (pinfunction "DIS_1") (pintype "input"))
      (node (ref "R10") (pin "2") (pinfunction "2_2") (pintype "passive"))
      (node (ref "R9") (pin "1") (pinfunction "1_1") (pintype "passive"))
    )
    (net (code "68") (name "Net-(IC27A-THR)") (class "Default")
      (node (ref "C6") (pin "1") (pinfunction "1_1") (pintype "passive"))
      (node (ref "IC27") (pin "2") (pinfunction "THR_2") (pintype "input"))
      (node (ref "IC27") (pin "6") (pinfunction "TR_6") (pintype "input"))
      (node (ref "R11") (pin "A") (pinfunction "A_A") (pintype "passive"))
      (node (ref "R11") (pin "S") (pinfunction "S_S") (pintype "passive"))
    )
    (net (code "69") (name "Net-(IC27B-CV)") (class "Default")
      (node (ref "C5") (pin "1") (pinfunction "1_1") (pintype "passive"))
      (node (ref "IC27") (pin "11") (pinfunction "CV_11") (pintype "input"))
    )
    (net (code "70") (name "Net-(IC27B-DIS)") (class "Default")
      (node (ref "IC27") (pin "13") (pinfunction "DIS_13") (pintype "input"))
      (node (ref "R3") (pin "1") (pinfunction "1_1") (pintype "passive"))
      (node (ref "R4") (pin "2") (pinfunction "2_2") (pintype "passive"))
    )
    (net (code "71") (name "Net-(IC27B-THR)") (class "Default")
      (node (ref "C4") (pin "1") (pinfunction "1_1") (pintype "passive"))
      (node (ref "IC27") (pin "12") (pinfunction "THR_12") (pintype "input"))
      (node (ref "IC27") (pin "8") (pinfunction "TR_8") (pintype "input"))
      (node (ref "R4") (pin "1") (pinfunction "1_1") (pintype "passive"))
    )
    (net (code "72") (name "Net-(LED1-PadA)") (class "Default")
      (node (ref "LED1") (pin "A") (pinfunction "A_A") (pintype "passive"))
      (node (ref "R12") (pin "1") (pinfunction "1_1") (pintype "passive"))
    )
    (net (code "73") (name "Net-(R10-Pad1)") (class "Default")
      (node (ref "R10") (pin "1") (pinfunction "1_1") (pintype "passive"))
      (node (ref "R11") (pin "E") (pinfunction "E_E") (pintype "passive"))
    )
    (net (code "74") (name "Net-(X1-Pad4)") (class "Default")
      (node (ref "X1") (pin "4") (pinfunction "4_4") (pintype "passive"))
      (node (ref "X1") (pin "6") (pinfunction "6_6") (pintype "passive"))
    )
    (net (code "75") (name "Net-(X1-Pad7)") (class "Default")
      (node (ref "X1") (pin "7") (pinfunction "7_7") (pintype "passive"))
      (node (ref "X1") (pin "8") (pinfunction "8_8") (pintype "passive"))
    )
    (net (code "76") (name "PIA-A0") (class "Default")
      (node (ref "CORE-IO") (pin "1") (pinfunction "1_1") (pintype "passive"))
      (node (ref "IC25") (pin "2") (pinfunction "A1_2") (pintype "bidirectional"))
    )
    (net (code "77") (name "PIA-A1") (class "Default")
      (node (ref "CORE-IO") (pin "2") (pinfunction "2_2") (pintype "passive"))
      (node (ref "IC25") (pin "3") (pinfunction "A2_3") (pintype "bidirectional"))
    )
    (net (code "78") (name "PIA-A2") (class "Default")
      (node (ref "CORE-IO") (pin "3") (pinfunction "3_3") (pintype "passive"))
      (node (ref "IC25") (pin "4") (pinfunction "A3_4") (pintype "bidirectional"))
    )
    (net (code "79") (name "PIA-A3") (class "Default")
      (node (ref "CORE-IO") (pin "4") (pinfunction "4_4") (pintype "passive"))
      (node (ref "IC25") (pin "5") (pinfunction "A4_5") (pintype "bidirectional"))
    )
    (net (code "80") (name "PIA-A4") (class "Default")
      (node (ref "CORE-IO") (pin "5") (pinfunction "5_5") (pintype "passive"))
      (node (ref "IC25") (pin "6") (pinfunction "A5_6") (pintype "bidirectional"))
    )
    (net (code "81") (name "PIA-A5") (class "Default")
      (node (ref "CORE-IO") (pin "6") (pinfunction "6_6") (pintype "passive"))
      (node (ref "IC25") (pin "7") (pinfunction "A6_7") (pintype "bidirectional"))
    )
    (net (code "82") (name "PIA-A6") (class "Default")
      (node (ref "CORE-IO") (pin "7") (pinfunction "7_7") (pintype "passive"))
      (node (ref "IC25") (pin "8") (pinfunction "A7_8") (pintype "bidirectional"))
    )
    (net (code "83") (name "PIA-A7") (class "Default")
      (node (ref "CORE-IO") (pin "8") (pinfunction "8_8") (pintype "passive"))
      (node (ref "IC25") (pin "9") (pinfunction "A8_9") (pintype "bidirectional"))
    )
    (net (code "84") (name "PIA-B0") (class "Default")
      (node (ref "CORE-IO") (pin "13") (pinfunction "13_13") (pintype "passive"))
      (node (ref "IC26") (pin "2") (pinfunction "A1_2") (pintype "bidirectional"))
    )
    (net (code "85") (name "PIA-B1") (class "Default")
      (node (ref "CORE-IO") (pin "14") (pinfunction "14_14") (pintype "passive"))
      (node (ref "IC26") (pin "3") (pinfunction "A2_3") (pintype "bidirectional"))
    )
    (net (code "86") (name "PIA-B2") (class "Default")
      (node (ref "CORE-IO") (pin "15") (pinfunction "15_15") (pintype "passive"))
      (node (ref "IC26") (pin "4") (pinfunction "A3_4") (pintype "bidirectional"))
    )
    (net (code "87") (name "PIA-B3") (class "Default")
      (node (ref "CORE-IO") (pin "16") (pinfunction "16_16") (pintype "passive"))
      (node (ref "IC26") (pin "5") (pinfunction "A4_5") (pintype "bidirectional"))
    )
    (net (code "88") (name "PIA-B4") (class "Default")
      (node (ref "CORE-IO") (pin "17") (pinfunction "17_17") (pintype "passive"))
      (node (ref "IC26") (pin "6") (pinfunction "A5_6") (pintype "bidirectional"))
    )
    (net (code "89") (name "PIA-B5") (class "Default")
      (node (ref "CORE-IO") (pin "18") (pinfunction "18_18") (pintype "passive"))
      (node (ref "IC26") (pin "7") (pinfunction "A6_7") (pintype "bidirectional"))
    )
    (net (code "90") (name "PIA-B6") (class "Default")
      (node (ref "CORE-IO") (pin "19") (pinfunction "19_19") (pintype "passive"))
      (node (ref "IC26") (pin "8") (pinfunction "A7_8") (pintype "bidirectional"))
    )
    (net (code "91") (name "PIA-B7") (class "Default")
      (node (ref "CORE-IO") (pin "20") (pinfunction "20_20") (pintype "passive"))
      (node (ref "IC26") (pin "9") (pinfunction "A8_9") (pintype "bidirectional"))
    )
    (net (code "92") (name "RX") (class "Default")
      (node (ref "IC20") (pin "12") (pinfunction "R1OUT_12") (pintype "output"))
      (node (ref "IC21") (pin "2") (pinfunction "RXDATA_2") (pintype "input"))
    )
    (net (code "93") (name "RXD") (class "Default")
      (node (ref "IC20") (pin "13") (pinfunction "R1IN_13") (pintype "input"))
      (node (ref "X1") (pin "3") (pinfunction "3_3") (pintype "passive"))
    )
    (net (code "94") (name "R{slash}~{W}") (class "Default")
      (node (ref "IC17") (pin "34") (pinfunction "R/~{W}_34") (pintype "output"))
      (node (ref "IC21") (pin "13") (pinfunction "R/~{W}_13") (pintype "input"))
      (node (ref "IC22") (pin "27") (pinfunction "~{WE}_27") (pintype "input"))
      (node (ref "IC24") (pin "21") (pinfunction "R/~{W}_21") (pintype "input"))
    )
    (net (code "95") (name "TX") (class "Default")
      (node (ref "IC20") (pin "11") (pinfunction "T1IN_11") (pintype "input"))
      (node (ref "IC21") (pin "6") (pinfunction "TXDATA_6") (pintype "output"))
    )
    (net (code "96") (name "TXD") (class "Default")
      (node (ref "IC20") (pin "14") (pinfunction "T1OUT_14") (pintype "output"))
      (node (ref "X1") (pin "2") (pinfunction "2_2") (pintype "passive"))
    )
    (net (code "97") (name "VCC") (class "Default")
      (node (ref "BYP17") (pin "1") (pinfunction "1_1") (pintype "passive"))
      (node (ref "BYP18") (pin "1") (pinfunction "1_1") (pintype "passive"))
      (node (ref "BYP19") (pin "1") (pinfunction "1_1") (pintype "passive"))
      (node (ref "BYP20") (pin "1") (pinfunction "1_1") (pintype "passive"))
      (node (ref "BYP21") (pin "1") (pinfunction "1_1") (pintype "passive"))
      (node (ref "BYP22") (pin "1") (pinfunction "1_1") (pintype "passive"))
      (node (ref "BYP23") (pin "1") (pinfunction "1_1") (pintype "passive"))
      (node (ref "BYP24") (pin "1") (pinfunction "1_1") (pintype "passive"))
      (node (ref "BYP25") (pin "1") (pinfunction "1_1") (pintype "passive"))
      (node (ref "BYP26") (pin "1") (pinfunction "1_1") (pintype "passive"))
      (node (ref "BYP27") (pin "1") (pinfunction "1_1") (pintype "passive"))
      (node (ref "BYP28") (pin "1") (pinfunction "1_1") (pintype "passive"))
      (node (ref "BYP29") (pin "1") (pinfunction "1_1") (pintype "passive"))
      (node (ref "C10") (pin "1") (pinfunction "1_1") (pintype "passive"))
      (node (ref "CORE-IO") (pin "12") (pinfunction "12_12") (pintype "passive"))
      (node (ref "CORE-IO") (pin "9") (pinfunction "9_9") (pintype "passive"))
      (node (ref "IC17") (pin "35") (pinfunction "VCCSTB_35") (pintype "input"))
      (node (ref "IC17") (pin "36") (pinfunction "RE_36") (pintype "input"))
      (node (ref "IC17") (pin "8") (pinfunction "VCC_8") (pintype "power_in"))
      (node (ref "IC21") (pin "10") (pinfunction "CS1_10") (pintype "input"))
      (node (ref "IC21") (pin "12") (pinfunction "VCC_12") (pintype "power_in"))
      (node (ref "IC21") (pin "8") (pinfunction "CS0_8") (pintype "input"))
      (node (ref "IC22") (pin "28") (pinfunction "VCC_28") (pintype "power_in"))
      (node (ref "IC23") (pin "1") (pinfunction "VPP_1") (pintype "input"))
      (node (ref "IC23") (pin "27") (pinfunction "~{PGM}_27") (pintype "passive"))
      (node (ref "IC23") (pin "28") (pinfunction "VCC_28") (pintype "power_in"))
      (node (ref "IC24") (pin "20") (pinfunction "VCC_20") (pintype "power_in"))
      (node (ref "IC24") (pin "22") (pinfunction "CS0_22") (pintype "input"))
      (node (ref "IC24") (pin "24") (pinfunction "CS1_24") (pintype "input"))
      (node (ref "IC27") (pin "10") (pinfunction "R_10") (pintype "input"))
      (node (ref "IC27") (pin "14") (pinfunction "V+_14") (pintype "power_in"))
      (node (ref "IC27") (pin "4") (pinfunction "R_4") (pintype "input"))
      (node (ref "IC29") (pin "1") (pinfunction "VPP_1") (pintype "input"))
      (node (ref "JP2") (pin "2") (pinfunction "2_2") (pintype "passive"))
      (node (ref "JP4") (pin "2") (pinfunction "2_2") (pintype "passive"))
      (node (ref "R1") (pin "2") (pinfunction "2_2") (pintype "passive"))
      (node (ref "R12") (pin "2") (pinfunction "2_2") (pintype "passive"))
      (node (ref "R14") (pin "2") (pinfunction "2_2") (pintype "passive"))
      (node (ref "R2") (pin "2") (pinfunction "2_2") (pintype "passive"))
      (node (ref "R3") (pin "2") (pinfunction "2_2") (pintype "passive"))
      (node (ref "R5") (pin "2") (pinfunction "2_2") (pintype "passive"))
      (node (ref "R6") (pin "2") (pinfunction "2_2") (pintype "passive"))
      (node (ref "R7") (pin "2") (pinfunction "2_2") (pintype "passive"))
      (node (ref "R8") (pin "2") (pinfunction "2_2") (pintype "passive"))
      (node (ref "R9") (pin "2") (pinfunction "2_2") (pintype "passive"))
    )
    (net (code "98") (name "VMA") (class "Default")
      (node (ref "IC17") (pin "5") (pinfunction "VMA_5") (pintype "output"))
      (node (ref "IC18") (pin "9") (pinfunction "I0_9") (pintype "input"))
    )
    (net (code "99") (name "unconnected-(IC17A-BA-Pad7)") (class "Default")
      (node (ref "IC17") (pin "7") (pinfunction "BA_7") (pintype "output"))
    )
    (net (code "100") (name "unconnected-(IC19A-Y0-Pad15)") (class "Default")
      (node (ref "IC19") (pin "15") (pinfunction "Y0_15") (pintype "output"))
    )
    (net (code "101") (name "unconnected-(IC19A-Y1-Pad14)") (class "Default")
      (node (ref "IC19") (pin "14") (pinfunction "Y1_14") (pintype "output"))
    )
    (net (code "102") (name "unconnected-(IC19A-Y2-Pad13)") (class "Default")
      (node (ref "IC19") (pin "13") (pinfunction "Y2_13") (pintype "output"))
    )
    (net (code "103") (name "unconnected-(IC19A-Y3-Pad12)") (class "Default")
      (node (ref "IC19") (pin "12") (pinfunction "Y3_12") (pintype "output"))
    )
    (net (code "104") (name "unconnected-(IC19A-Y4-Pad11)") (class "Default")
      (node (ref "IC19") (pin "11") (pinfunction "Y4_11") (pintype "output"))
    )
    (net (code "105") (name "unconnected-(IC19A-Y5-Pad10)") (class "Default")
      (node (ref "IC19") (pin "10") (pinfunction "Y5_10") (pintype "output"))
    )
    (net (code "106") (name "unconnected-(IC20A-R2OUT-Pad9)") (class "Default")
      (node (ref "IC20") (pin "9") (pinfunction "R2OUT_9") (pintype "output"))
    )
    (net (code "107") (name "unconnected-(IC22-NC-Pad1)") (class "Default")
      (node (ref "IC22") (pin "1") (pinfunction "NC_1") (pintype "no_connect"))
    )
    (net (code "108") (name "unconnected-(IC28A-Y0-Pad4)") (class "Default")
      (node (ref "IC28") (pin "4") (pinfunction "Y0_4") (pintype "output"))
    )
    (net (code "109") (name "unconnected-(IC28B-Y1-Pad11)") (class "Default")
      (node (ref "IC28") (pin "11") (pinfunction "Y1_11") (pintype "output"))
    )
    (net (code "110") (name "unconnected-(IC28B-Y2-Pad10)") (class "Default")
      (node (ref "IC28") (pin "10") (pinfunction "Y2_10") (pintype "output"))
    )
    (net (code "111") (name "unconnected-(X1-Pad1)") (class "Default")
      (node (ref "X1") (pin "1") (pinfunction "1_1") (pintype "passive"))
    )
    (net (code "112") (name "unconnected-(X1-Pad9)") (class "Default")
      (node (ref "X1") (pin "9") (pinfunction "9_9") (pintype "passive"))
    )
    (net (code "113") (name "~{4-B}") (class "Default")
      (node (ref "IC28") (pin "7") (pinfunction "Y3_7") (pintype "output"))
      (node (ref "IC29") (pin "20") (pinfunction "~{CE}_20") (pintype "input"))
      (node (ref "IC29") (pin "22") (pinfunction "~{OE}_22") (pintype "input"))
    )
    (net (code "114") (name "~{0123}") (class "Default")
      (node (ref "IC19") (pin "5") (pinfunction "G2B_5") (pintype "input"))
      (node (ref "IC22") (pin "20") (pinfunction "~{CS1}_20") (pintype "input"))
      (node (ref "IC22") (pin "22") (pinfunction "~{OE}_22") (pintype "input"))
      (node (ref "IC28") (pin "5") (pinfunction "Y1_5") (pintype "output"))
    )
    (net (code "115") (name "~{CDEF}") (class "Default")
      (node (ref "IC23") (pin "20") (pinfunction "~{CE}_20") (pintype "input"))
      (node (ref "IC23") (pin "22") (pinfunction "~{OE}_22") (pintype "input"))
      (node (ref "IC28") (pin "6") (pinfunction "Y2_6") (pintype "output"))
    )
    (net (code "116") (name "~{EP1}") (class "Default")
      (node (ref "IC28") (pin "2") (pinfunction "A_2") (pintype "input"))
      (node (ref "IC28") (pin "9") (pinfunction "Y3_9") (pintype "output"))
    )
    (net (code "117") (name "~{HLT}") (class "Default")
      (node (ref "IC17") (pin "2") (pinfunction "HALT_2") (pintype "input"))
      (node (ref "R5") (pin "1") (pinfunction "1_1") (pintype "passive"))
    )
    (net (code "118") (name "~{IO-E}") (class "Default")
      (node (ref "IC19") (pin "9") (pinfunction "Y6_9") (pintype "output"))
      (node (ref "IC24") (pin "23") (pinfunction "CS2_23") (pintype "input"))
    )
    (net (code "119") (name "~{IO-F}") (class "Default")
      (node (ref "IC19") (pin "7") (pinfunction "Y7_7") (pintype "output"))
      (node (ref "IC21") (pin "9") (pinfunction "CS2_9") (pintype "input"))
    )
    (net (code "120") (name "~{IRQ}") (class "Default")
      (node (ref "IC17") (pin "4") (pinfunction "IRQ_4") (pintype "input"))
      (node (ref "IC24") (pin "37") (pinfunction "IRQB_37") (pintype "open_collector"))
      (node (ref "IC24") (pin "38") (pinfunction "IRQA_38") (pintype "open_collector"))
      (node (ref "R7") (pin "1") (pinfunction "1_1") (pintype "passive"))
    )
    (net (code "121") (name "~{NMI}") (class "Default")
      (node (ref "IC17") (pin "6") (pinfunction "NMI_6") (pintype "input"))
      (node (ref "IC21") (pin "7") (pinfunction "IRQ_7") (pintype "output"))
      (node (ref "R6") (pin "1") (pinfunction "1_1") (pintype "passive"))
    )
    (net (code "122") (name "~{RST}") (class "Default")
      (node (ref "IC17") (pin "40") (pinfunction "RESET_40") (pintype "input"))
      (node (ref "IC18") (pin "6") (pinfunction "O_6") (pintype "output"))
      (node (ref "IC24") (pin "34") (pinfunction "RESET_34") (pintype "input"))
    )
  )
)
